# Fyp_SCH_FINAL.net
KiCad netlist of a schematic drawn in EasyEDA
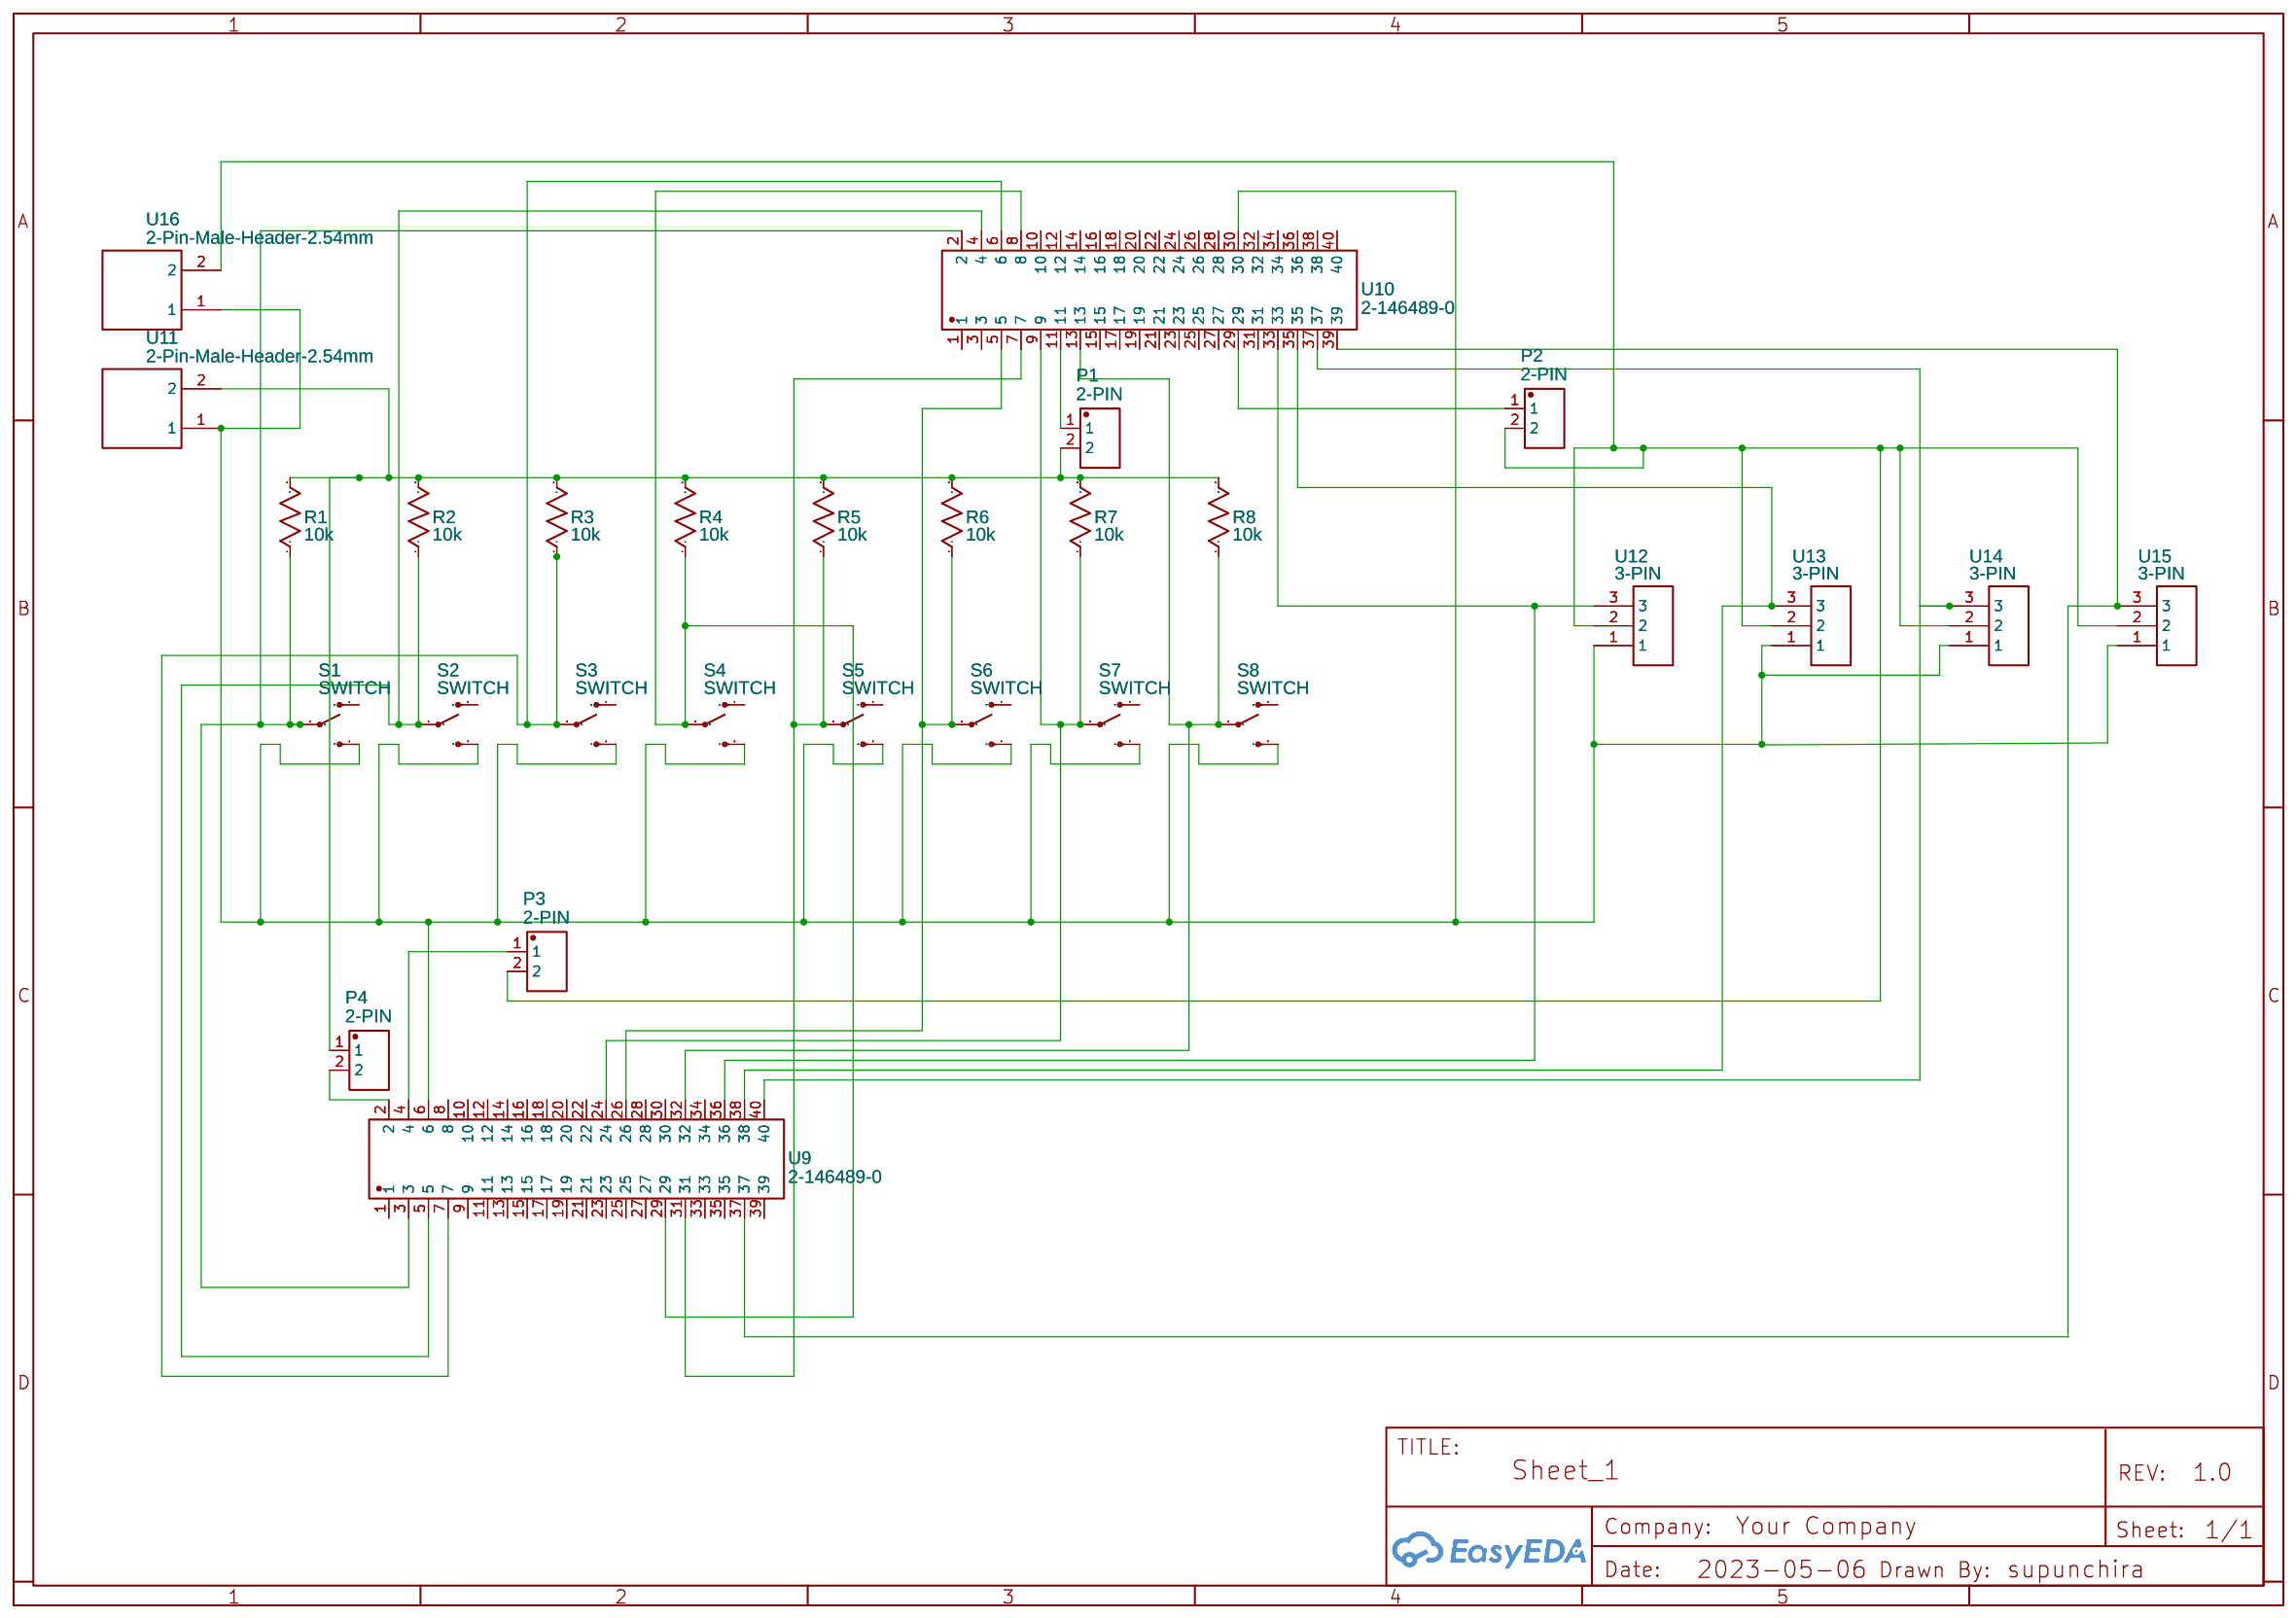
[diagram p0: schematic sheet]

(export (version "E")
  (design (tool "Eeschema 10.0.6"))
  (components
    (comp (ref "P1")
      (value "2-PIN")
      (fields
        (field (name "BOM_Manufacturer Part") "Terminals/WJ2EDGV-5.08-8P")
        (field (name "BOM_Supplier Part") "C23595")
      )
      (libsource (lib "") (part "2-PIN-MALE-CONNECTOR COPY"))
    )
    (comp (ref "P2")
      (value "2-PIN")
      (fields
        (field (name "BOM_Manufacturer Part") "Terminals/WJ2EDGV-5.08-8P")
        (field (name "BOM_Supplier Part") "C23595")
      )
      (libsource (lib "") (part "2-PIN-MALE-CONNECTOR COPY"))
    )
    (comp (ref "P3")
      (value "2-PIN")
      (fields
        (field (name "BOM_Manufacturer Part") "Terminals/WJ2EDGV-5.08-8P")
        (field (name "BOM_Supplier Part") "C23595")
      )
      (libsource (lib "") (part "2-PIN-MALE-CONNECTOR COPY"))
    )
    (comp (ref "P4")
      (value "2-PIN")
      (fields
        (field (name "BOM_Manufacturer Part") "Terminals/WJ2EDGV-5.08-8P")
        (field (name "BOM_Supplier Part") "C23595")
      )
      (libsource (lib "") (part "2-PIN-MALE-CONNECTOR COPY"))
    )
    (comp (ref "R1") (value "10k") (libsource (lib "") (part "R_AXIAL-0.3_US")))
    (comp (ref "R2") (value "10k") (libsource (lib "") (part "R_AXIAL-0.3_US")))
    (comp (ref "R3") (value "10k") (libsource (lib "") (part "R_AXIAL-0.3_US")))
    (comp (ref "R4") (value "10k") (libsource (lib "") (part "R_AXIAL-0.3_US")))
    (comp (ref "R5") (value "10k") (libsource (lib "") (part "R_AXIAL-0.3_US")))
    (comp (ref "R6") (value "10k") (libsource (lib "") (part "R_AXIAL-0.3_US")))
    (comp (ref "R7") (value "10k") (libsource (lib "") (part "R_AXIAL-0.3_US")))
    (comp (ref "R8") (value "10k") (libsource (lib "") (part "R_AXIAL-0.3_US")))
    (comp (ref "S1") (value "SWITCH") (libsource (lib "") (part "SWITCH-SPDT 3MM 10X5MM")))
    (comp (ref "S2") (value "SWITCH") (libsource (lib "") (part "SWITCH-SPDT 3MM 10X5MM")))
    (comp (ref "S3") (value "SWITCH") (libsource (lib "") (part "SWITCH-SPDT 3MM 10X5MM")))
    (comp (ref "S4") (value "SWITCH") (libsource (lib "") (part "SWITCH-SPDT 3MM 10X5MM")))
    (comp (ref "S5") (value "SWITCH") (libsource (lib "") (part "SWITCH-SPDT 3MM 10X5MM")))
    (comp (ref "S6") (value "SWITCH") (libsource (lib "") (part "SWITCH-SPDT 3MM 10X5MM")))
    (comp (ref "S7") (value "SWITCH") (libsource (lib "") (part "SWITCH-SPDT 3MM 10X5MM")))
    (comp (ref "S8") (value "SWITCH") (libsource (lib "") (part "SWITCH-SPDT 3MM 10X5MM")))
    (comp (ref "U9")
      (value "2-146489-0")
      (fields (field (name "BOM_Supplier Part") "C3334839"))
      (libsource (lib "") (part "2-146489-0"))
    )
    (comp (ref "U10")
      (value "2-146489-0")
      (fields (field (name "BOM_Supplier Part") "C3334839"))
      (libsource (lib "") (part "2-146489-0"))
    )
    (comp (ref "U11")
      (value "2-Pin-Male-Header-2.54mm")
      (libsource (lib "") (part "2-Pin-Male-Header-2.54mm"))
    )
    (comp (ref "U12") (value "3-PIN") (libsource (lib "") (part "3-PIN")))
    (comp (ref "U13") (value "3-PIN") (libsource (lib "") (part "3-PIN")))
    (comp (ref "U14") (value "3-PIN") (libsource (lib "") (part "3-PIN")))
    (comp (ref "U15") (value "3-PIN") (libsource (lib "") (part "3-PIN")))
    (comp (ref "U16")
      (value "2-Pin-Male-Header-2.54mm")
      (libsource (lib "") (part "2-Pin-Male-Header-2.54mm"))
    )
  )
  (nets
    (net (code "1") (name "Net-(P1-Pad1)") (class "Default")
      (node (ref "P1") (pin "1") (pinfunction "1_1") (pintype "unspecified"))
      (node (ref "U10") (pin "11") (pinfunction "11_11") (pintype "unspecified"))
    )
    (net (code "2") (name "Net-(P1-Pad2)") (class "Default")
      (node (ref "P1") (pin "2") (pinfunction "2_2") (pintype "unspecified"))
      (node (ref "P4") (pin "1") (pinfunction "1_1") (pintype "unspecified"))
      (node (ref "R1") (pin "2") (pinfunction "2_2") (pintype "unspecified"))
      (node (ref "R2") (pin "2") (pinfunction "2_2") (pintype "unspecified"))
      (node (ref "R3") (pin "2") (pinfunction "2_2") (pintype "unspecified"))
      (node (ref "R4") (pin "2") (pinfunction "2_2") (pintype "unspecified"))
      (node (ref "R5") (pin "2") (pinfunction "2_2") (pintype "unspecified"))
      (node (ref "R6") (pin "2") (pinfunction "2_2") (pintype "unspecified"))
      (node (ref "R7") (pin "2") (pinfunction "2_2") (pintype "unspecified"))
      (node (ref "R8") (pin "2") (pinfunction "2_2") (pintype "unspecified"))
      (node (ref "U11") (pin "2") (pinfunction "2_2") (pintype "unspecified"))
    )
    (net (code "3") (name "Net-(P2-Pad1)") (class "Default")
      (node (ref "P2") (pin "1") (pinfunction "1_1") (pintype "unspecified"))
      (node (ref "U10") (pin "29") (pinfunction "29_29") (pintype "unspecified"))
    )
    (net (code "4") (name "Net-(P2-Pad2)") (class "Default")
      (node (ref "P2") (pin "2") (pinfunction "2_2") (pintype "unspecified"))
      (node (ref "P3") (pin "2") (pinfunction "2_2") (pintype "unspecified"))
      (node (ref "U12") (pin "2") (pinfunction "2_2") (pintype "unspecified"))
      (node (ref "U13") (pin "2") (pinfunction "2_2") (pintype "unspecified"))
      (node (ref "U14") (pin "2") (pinfunction "2_2") (pintype "unspecified"))
      (node (ref "U15") (pin "2") (pinfunction "2_2") (pintype "unspecified"))
      (node (ref "U16") (pin "2") (pinfunction "2_2") (pintype "unspecified"))
    )
    (net (code "5") (name "Net-(P3-Pad1)") (class "Default")
      (node (ref "P3") (pin "1") (pinfunction "1_1") (pintype "unspecified"))
      (node (ref "U9") (pin "4") (pinfunction "4_4") (pintype "unspecified"))
    )
    (net (code "6") (name "Net-(P4-Pad2)") (class "Default")
      (node (ref "P4") (pin "2") (pinfunction "2_2") (pintype "unspecified"))
      (node (ref "U9") (pin "2") (pinfunction "2_2") (pintype "unspecified"))
    )
    (net (code "7") (name "Net-(S1-P)") (class "Default")
      (node (ref "R1") (pin "1") (pinfunction "1_1") (pintype "unspecified"))
      (node (ref "S1") (pin "2") (pinfunction "P_2") (pintype "unspecified"))
      (node (ref "U10") (pin "2") (pinfunction "2_2") (pintype "unspecified"))
      (node (ref "U9") (pin "3") (pinfunction "3_3") (pintype "unspecified"))
    )
    (net (code "8") (name "Net-(S1-S)") (class "Default")
      (node (ref "S1") (pin "3") (pinfunction "S_3") (pintype "unspecified"))
      (node (ref "S2") (pin "3") (pinfunction "S_3") (pintype "unspecified"))
      (node (ref "S3") (pin "3") (pinfunction "S_3") (pintype "unspecified"))
      (node (ref "S4") (pin "3") (pinfunction "S_3") (pintype "unspecified"))
      (node (ref "S5") (pin "3") (pinfunction "S_3") (pintype "unspecified"))
      (node (ref "S6") (pin "3") (pinfunction "S_3") (pintype "unspecified"))
      (node (ref "S7") (pin "3") (pinfunction "S_3") (pintype "unspecified"))
      (node (ref "S8") (pin "3") (pinfunction "S_3") (pintype "unspecified"))
      (node (ref "U10") (pin "30") (pinfunction "30_30") (pintype "unspecified"))
      (node (ref "U11") (pin "1") (pinfunction "1_1") (pintype "unspecified"))
      (node (ref "U12") (pin "1") (pinfunction "1_1") (pintype "unspecified"))
      (node (ref "U13") (pin "1") (pinfunction "1_1") (pintype "unspecified"))
      (node (ref "U14") (pin "1") (pinfunction "1_1") (pintype "unspecified"))
      (node (ref "U15") (pin "1") (pinfunction "1_1") (pintype "unspecified"))
      (node (ref "U16") (pin "1") (pinfunction "1_1") (pintype "unspecified"))
      (node (ref "U9") (pin "6") (pinfunction "6_6") (pintype "unspecified"))
    )
    (net (code "9") (name "Net-(S2-P)") (class "Default")
      (node (ref "R2") (pin "1") (pinfunction "1_1") (pintype "unspecified"))
      (node (ref "S2") (pin "2") (pinfunction "P_2") (pintype "unspecified"))
      (node (ref "U10") (pin "4") (pinfunction "4_4") (pintype "unspecified"))
      (node (ref "U9") (pin "5") (pinfunction "5_5") (pintype "unspecified"))
    )
    (net (code "10") (name "Net-(S3-P)") (class "Default")
      (node (ref "R3") (pin "1") (pinfunction "1_1") (pintype "unspecified"))
      (node (ref "S3") (pin "2") (pinfunction "P_2") (pintype "unspecified"))
      (node (ref "U10") (pin "6") (pinfunction "6_6") (pintype "unspecified"))
      (node (ref "U9") (pin "7") (pinfunction "7_7") (pintype "unspecified"))
    )
    (net (code "11") (name "Net-(S4-P)") (class "Default")
      (node (ref "R4") (pin "1") (pinfunction "1_1") (pintype "unspecified"))
      (node (ref "S4") (pin "2") (pinfunction "P_2") (pintype "unspecified"))
      (node (ref "U10") (pin "8") (pinfunction "8_8") (pintype "unspecified"))
      (node (ref "U9") (pin "29") (pinfunction "29_29") (pintype "unspecified"))
    )
    (net (code "12") (name "Net-(S5-P)") (class "Default")
      (node (ref "R5") (pin "1") (pinfunction "1_1") (pintype "unspecified"))
      (node (ref "S5") (pin "2") (pinfunction "P_2") (pintype "unspecified"))
      (node (ref "U10") (pin "7") (pinfunction "7_7") (pintype "unspecified"))
      (node (ref "U9") (pin "31") (pinfunction "31_31") (pintype "unspecified"))
    )
    (net (code "13") (name "Net-(S6-P)") (class "Default")
      (node (ref "R6") (pin "1") (pinfunction "1_1") (pintype "unspecified"))
      (node (ref "S6") (pin "2") (pinfunction "P_2") (pintype "unspecified"))
      (node (ref "U10") (pin "5") (pinfunction "5_5") (pintype "unspecified"))
      (node (ref "U9") (pin "26") (pinfunction "26_26") (pintype "unspecified"))
    )
    (net (code "14") (name "Net-(S7-P)") (class "Default")
      (node (ref "R7") (pin "1") (pinfunction "1_1") (pintype "unspecified"))
      (node (ref "S7") (pin "2") (pinfunction "P_2") (pintype "unspecified"))
      (node (ref "U10") (pin "9") (pinfunction "9_9") (pintype "unspecified"))
      (node (ref "U9") (pin "24") (pinfunction "24_24") (pintype "unspecified"))
    )
    (net (code "15") (name "Net-(S8-P)") (class "Default")
      (node (ref "R8") (pin "1") (pinfunction "1_1") (pintype "unspecified"))
      (node (ref "S8") (pin "2") (pinfunction "P_2") (pintype "unspecified"))
      (node (ref "U10") (pin "13") (pinfunction "13_13") (pintype "unspecified"))
      (node (ref "U9") (pin "32") (pinfunction "32_32") (pintype "unspecified"))
    )
    (net (code "16") (name "Net-(U10-Pad33)") (class "Default")
      (node (ref "U10") (pin "33") (pinfunction "33_33") (pintype "unspecified"))
      (node (ref "U12") (pin "3") (pinfunction "3_3") (pintype "unspecified"))
      (node (ref "U9") (pin "36") (pinfunction "36_36") (pintype "unspecified"))
    )
    (net (code "17") (name "Net-(U10-Pad35)") (class "Default")
      (node (ref "U10") (pin "35") (pinfunction "35_35") (pintype "unspecified"))
      (node (ref "U13") (pin "3") (pinfunction "3_3") (pintype "unspecified"))
      (node (ref "U9") (pin "38") (pinfunction "38_38") (pintype "unspecified"))
    )
    (net (code "18") (name "Net-(U10-Pad37)") (class "Default")
      (node (ref "U10") (pin "37") (pinfunction "37_37") (pintype "unspecified"))
      (node (ref "U14") (pin "3") (pinfunction "3_3") (pintype "unspecified"))
      (node (ref "U9") (pin "40") (pinfunction "40_40") (pintype "unspecified"))
    )
    (net (code "19") (name "Net-(U10-Pad39)") (class "Default")
      (node (ref "U10") (pin "39") (pinfunction "39_39") (pintype "unspecified"))
      (node (ref "U15") (pin "3") (pinfunction "3_3") (pintype "unspecified"))
      (node (ref "U9") (pin "37") (pinfunction "37_37") (pintype "unspecified"))
    )
    (net (code "20") (name "unconnected-(S1-O-Pad1)") (class "Default")
      (node (ref "S1") (pin "1") (pinfunction "O_1") (pintype "unspecified"))
    )
    (net (code "21") (name "unconnected-(S2-O-Pad1)") (class "Default")
      (node (ref "S2") (pin "1") (pinfunction "O_1") (pintype "unspecified"))
    )
    (net (code "22") (name "unconnected-(S3-O-Pad1)") (class "Default")
      (node (ref "S3") (pin "1") (pinfunction "O_1") (pintype "unspecified"))
    )
    (net (code "23") (name "unconnected-(S4-O-Pad1)") (class "Default")
      (node (ref "S4") (pin "1") (pinfunction "O_1") (pintype "unspecified"))
    )
    (net (code "24") (name "unconnected-(S5-O-Pad1)") (class "Default")
      (node (ref "S5") (pin "1") (pinfunction "O_1") (pintype "unspecified"))
    )
    (net (code "25") (name "unconnected-(S6-O-Pad1)") (class "Default")
      (node (ref "S6") (pin "1") (pinfunction "O_1") (pintype "unspecified"))
    )
    (net (code "26") (name "unconnected-(S7-O-Pad1)") (class "Default")
      (node (ref "S7") (pin "1") (pinfunction "O_1") (pintype "unspecified"))
    )
    (net (code "27") (name "unconnected-(S8-O-Pad1)") (class "Default")
      (node (ref "S8") (pin "1") (pinfunction "O_1") (pintype "unspecified"))
    )
    (net (code "28") (name "unconnected-(U9-Pad1)") (class "Default")
      (node (ref "U9") (pin "1") (pinfunction "1_1") (pintype "unspecified"))
    )
    (net (code "29") (name "unconnected-(U9-Pad8)") (class "Default")
      (node (ref "U9") (pin "8") (pinfunction "8_8") (pintype "unspecified"))
    )
    (net (code "30") (name "unconnected-(U9-Pad9)") (class "Default")
      (node (ref "U9") (pin "9") (pinfunction "9_9") (pintype "unspecified"))
    )
    (net (code "31") (name "unconnected-(U9-Pad10)") (class "Default")
      (node (ref "U9") (pin "10") (pinfunction "10_10") (pintype "unspecified"))
    )
    (net (code "32") (name "unconnected-(U9-Pad11)") (class "Default")
      (node (ref "U9") (pin "11") (pinfunction "11_11") (pintype "unspecified"))
    )
    (net (code "33") (name "unconnected-(U9-Pad12)") (class "Default")
      (node (ref "U9") (pin "12") (pinfunction "12_12") (pintype "unspecified"))
    )
    (net (code "34") (name "unconnected-(U9-Pad13)") (class "Default")
      (node (ref "U9") (pin "13") (pinfunction "13_13") (pintype "unspecified"))
    )
    (net (code "35") (name "unconnected-(U9-Pad14)") (class "Default")
      (node (ref "U9") (pin "14") (pinfunction "14_14") (pintype "unspecified"))
    )
    (net (code "36") (name "unconnected-(U9-Pad15)") (class "Default")
      (node (ref "U9") (pin "15") (pinfunction "15_15") (pintype "unspecified"))
    )
    (net (code "37") (name "unconnected-(U9-Pad16)") (class "Default")
      (node (ref "U9") (pin "16") (pinfunction "16_16") (pintype "unspecified"))
    )
    (net (code "38") (name "unconnected-(U9-Pad17)") (class "Default")
      (node (ref "U9") (pin "17") (pinfunction "17_17") (pintype "unspecified"))
    )
    (net (code "39") (name "unconnected-(U9-Pad18)") (class "Default")
      (node (ref "U9") (pin "18") (pinfunction "18_18") (pintype "unspecified"))
    )
    (net (code "40") (name "unconnected-(U9-Pad19)") (class "Default")
      (node (ref "U9") (pin "19") (pinfunction "19_19") (pintype "unspecified"))
    )
    (net (code "41") (name "unconnected-(U9-Pad20)") (class "Default")
      (node (ref "U9") (pin "20") (pinfunction "20_20") (pintype "unspecified"))
    )
    (net (code "42") (name "unconnected-(U9-Pad21)") (class "Default")
      (node (ref "U9") (pin "21") (pinfunction "21_21") (pintype "unspecified"))
    )
    (net (code "43") (name "unconnected-(U9-Pad22)") (class "Default")
      (node (ref "U9") (pin "22") (pinfunction "22_22") (pintype "unspecified"))
    )
    (net (code "44") (name "unconnected-(U9-Pad23)") (class "Default")
      (node (ref "U9") (pin "23") (pinfunction "23_23") (pintype "unspecified"))
    )
    (net (code "45") (name "unconnected-(U9-Pad25)") (class "Default")
      (node (ref "U9") (pin "25") (pinfunction "25_25") (pintype "unspecified"))
    )
    (net (code "46") (name "unconnected-(U9-Pad27)") (class "Default")
      (node (ref "U9") (pin "27") (pinfunction "27_27") (pintype "unspecified"))
    )
    (net (code "47") (name "unconnected-(U9-Pad28)") (class "Default")
      (node (ref "U9") (pin "28") (pinfunction "28_28") (pintype "unspecified"))
    )
    (net (code "48") (name "unconnected-(U9-Pad30)") (class "Default")
      (node (ref "U9") (pin "30") (pinfunction "30_30") (pintype "unspecified"))
    )
    (net (code "49") (name "unconnected-(U9-Pad33)") (class "Default")
      (node (ref "U9") (pin "33") (pinfunction "33_33") (pintype "unspecified"))
    )
    (net (code "50") (name "unconnected-(U9-Pad34)") (class "Default")
      (node (ref "U9") (pin "34") (pinfunction "34_34") (pintype "unspecified"))
    )
    (net (code "51") (name "unconnected-(U9-Pad35)") (class "Default")
      (node (ref "U9") (pin "35") (pinfunction "35_35") (pintype "unspecified"))
    )
    (net (code "52") (name "unconnected-(U9-Pad39)") (class "Default")
      (node (ref "U9") (pin "39") (pinfunction "39_39") (pintype "unspecified"))
    )
    (net (code "53") (name "unconnected-(U10-Pad1)") (class "Default")
      (node (ref "U10") (pin "1") (pinfunction "1_1") (pintype "unspecified"))
    )
    (net (code "54") (name "unconnected-(U10-Pad3)") (class "Default")
      (node (ref "U10") (pin "3") (pinfunction "3_3") (pintype "unspecified"))
    )
    (net (code "55") (name "unconnected-(U10-Pad10)") (class "Default")
      (node (ref "U10") (pin "10") (pinfunction "10_10") (pintype "unspecified"))
    )
    (net (code "56") (name "unconnected-(U10-Pad12)") (class "Default")
      (node (ref "U10") (pin "12") (pinfunction "12_12") (pintype "unspecified"))
    )
    (net (code "57") (name "unconnected-(U10-Pad14)") (class "Default")
      (node (ref "U10") (pin "14") (pinfunction "14_14") (pintype "unspecified"))
    )
    (net (code "58") (name "unconnected-(U10-Pad15)") (class "Default")
      (node (ref "U10") (pin "15") (pinfunction "15_15") (pintype "unspecified"))
    )
    (net (code "59") (name "unconnected-(U10-Pad16)") (class "Default")
      (node (ref "U10") (pin "16") (pinfunction "16_16") (pintype "unspecified"))
    )
    (net (code "60") (name "unconnected-(U10-Pad17)") (class "Default")
      (node (ref "U10") (pin "17") (pinfunction "17_17") (pintype "unspecified"))
    )
    (net (code "61") (name "unconnected-(U10-Pad18)") (class "Default")
      (node (ref "U10") (pin "18") (pinfunction "18_18") (pintype "unspecified"))
    )
    (net (code "62") (name "unconnected-(U10-Pad19)") (class "Default")
      (node (ref "U10") (pin "19") (pinfunction "19_19") (pintype "unspecified"))
    )
    (net (code "63") (name "unconnected-(U10-Pad20)") (class "Default")
      (node (ref "U10") (pin "20") (pinfunction "20_20") (pintype "unspecified"))
    )
    (net (code "64") (name "unconnected-(U10-Pad21)") (class "Default")
      (node (ref "U10") (pin "21") (pinfunction "21_21") (pintype "unspecified"))
    )
    (net (code "65") (name "unconnected-(U10-Pad22)") (class "Default")
      (node (ref "U10") (pin "22") (pinfunction "22_22") (pintype "unspecified"))
    )
    (net (code "66") (name "unconnected-(U10-Pad23)") (class "Default")
      (node (ref "U10") (pin "23") (pinfunction "23_23") (pintype "unspecified"))
    )
    (net (code "67") (name "unconnected-(U10-Pad24)") (class "Default")
      (node (ref "U10") (pin "24") (pinfunction "24_24") (pintype "unspecified"))
    )
    (net (code "68") (name "unconnected-(U10-Pad25)") (class "Default")
      (node (ref "U10") (pin "25") (pinfunction "25_25") (pintype "unspecified"))
    )
    (net (code "69") (name "unconnected-(U10-Pad26)") (class "Default")
      (node (ref "U10") (pin "26") (pinfunction "26_26") (pintype "unspecified"))
    )
    (net (code "70") (name "unconnected-(U10-Pad27)") (class "Default")
      (node (ref "U10") (pin "27") (pinfunction "27_27") (pintype "unspecified"))
    )
    (net (code "71") (name "unconnected-(U10-Pad28)") (class "Default")
      (node (ref "U10") (pin "28") (pinfunction "28_28") (pintype "unspecified"))
    )
    (net (code "72") (name "unconnected-(U10-Pad31)") (class "Default")
      (node (ref "U10") (pin "31") (pinfunction "31_31") (pintype "unspecified"))
    )
    (net (code "73") (name "unconnected-(U10-Pad32)") (class "Default")
      (node (ref "U10") (pin "32") (pinfunction "32_32") (pintype "unspecified"))
    )
    (net (code "74") (name "unconnected-(U10-Pad34)") (class "Default")
      (node (ref "U10") (pin "34") (pinfunction "34_34") (pintype "unspecified"))
    )
    (net (code "75") (name "unconnected-(U10-Pad36)") (class "Default")
      (node (ref "U10") (pin "36") (pinfunction "36_36") (pintype "unspecified"))
    )
    (net (code "76") (name "unconnected-(U10-Pad38)") (class "Default")
      (node (ref "U10") (pin "38") (pinfunction "38_38") (pintype "unspecified"))
    )
    (net (code "77") (name "unconnected-(U10-Pad40)") (class "Default")
      (node (ref "U10") (pin "40") (pinfunction "40_40") (pintype "unspecified"))
    )
  )
)
